# WIFI_module.net
KiCad netlist of a schematic drawn in Altium Designer
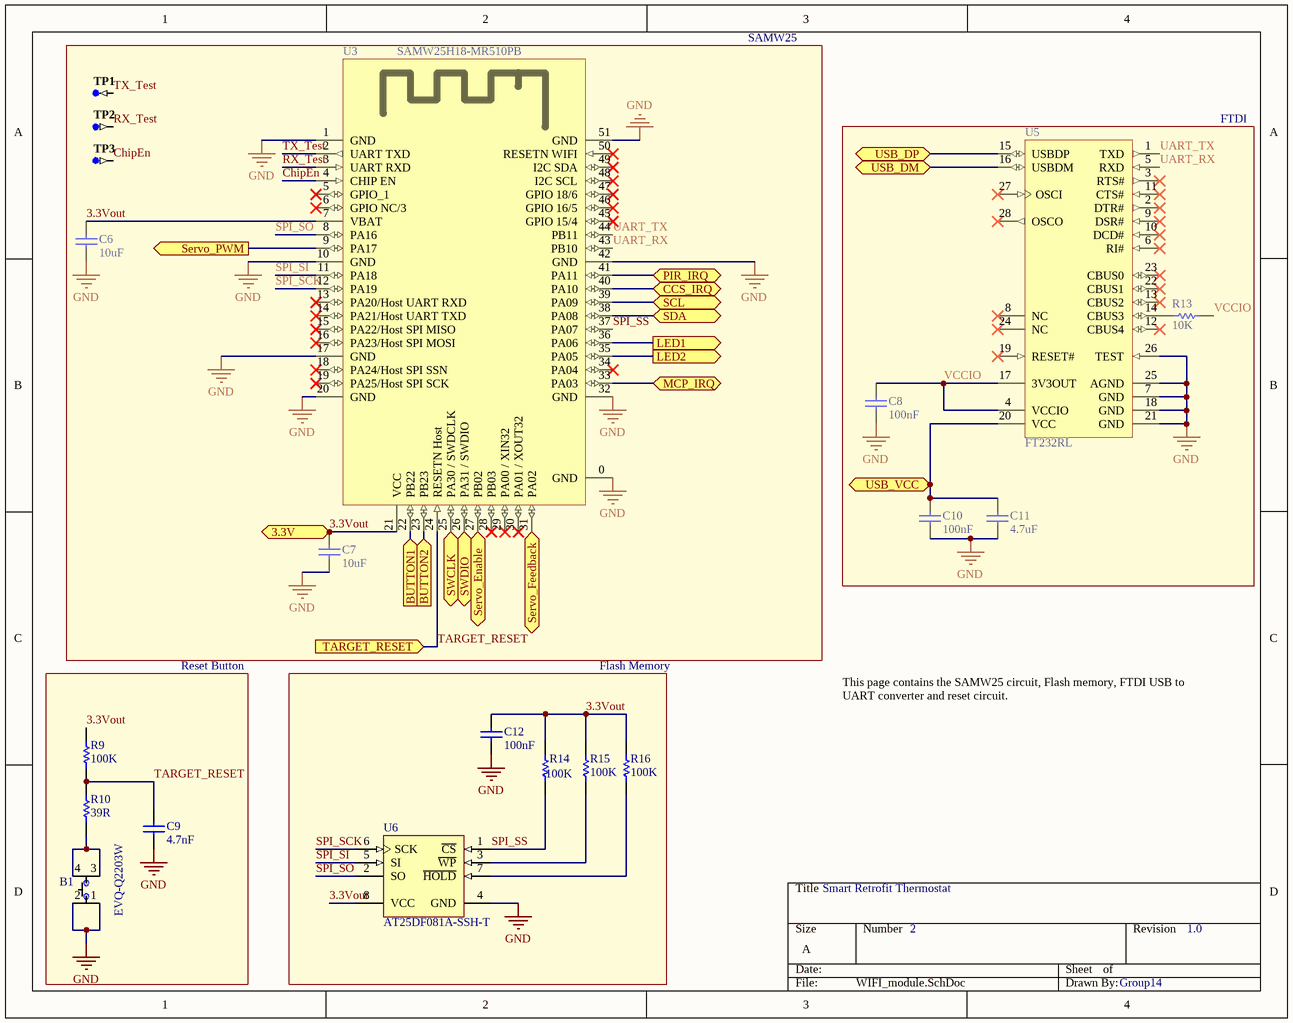
[diagram p0: WIFI_module.SchDoc]

(export (version "E")
  (design (tool "Eeschema 10.0.6"))
  (components
    (comp (ref "B1")
      (value "EVQ-Q2203W")
      (footprint "EVQ-Q2203W")
      (description "SWITCH TACTILE SPST-NO 0.02A 15V")
      (fields (field (name "MANUFACTURER") "Panasonic Electronic Components"))
      (libsource (lib "ese516_baseComponents") (part "EVQ-Q2203W"))
    )
    (comp (ref "C6")
      (value "10uF")
      (footprint "CAPC0805(2012)100_L")
      (description "CAP 10uF 16V ±20% 0805 (2012 Metric) Thickness 1mm SMD")
      (fields (field (name "TOLERANCE") "Â±20%"))
      (libsource (lib "Altium Content Vault") (part "CMP-1036-04930-1"))
    )
    (comp (ref "C7")
      (value "10uF")
      (footprint "CAPC0805(2012)100_L")
      (description "CAP 10uF 16V ±20% 0805 (2012 Metric) Thickness 1mm SMD")
      (fields (field (name "TOLERANCE") "Â±20%"))
      (libsource (lib "Altium Content Vault") (part "CMP-1036-04930-1"))
    )
    (comp (ref "C8")
      (value "100nF")
      (footprint "CAPC0805(2012)145_M")
      (description "CAP 100nF 16V ±20% 0805 (2012 Metric) Thickness 1.45mm SMD")
      (fields (field (name "TOLERANCE") "Â±20%"))
      (libsource (lib "Altium Content Vault") (part "CAP"))
    )
    (comp (ref "C9")
      (value "4.7nF")
      (footprint "CAPC0805(2012)100_L")
      (description "CAP 4.7nF 16V ±20% 0805 (2012 Metric) Thickness 1mm SMD")
      (fields (field (name "TOLERANCE") "Â±20%"))
      (libsource (lib "Altium Content Vault") (part "CAP"))
    )
    (comp (ref "C10")
      (value "100nF")
      (footprint "CAPC0805(2012)145_M")
      (description "CAP 100nF 16V ±20% 0805 (2012 Metric) Thickness 1.45mm SMD")
      (fields (field (name "TOLERANCE") "Â±20%"))
      (libsource (lib "Altium Content Vault") (part "CAP"))
    )
    (comp (ref "C11")
      (value "4.7uF")
      (footprint "CAPC0805(2012)155_L")
      (description "CAP 4.7uF 10V ±10% 0805 (2012 Metric) Thickness 1.55mm SMD")
      (fields (field (name "TOLERANCE") "Â±10%"))
      (libsource (lib "Altium Content Vault") (part "CAP"))
    )
    (comp (ref "C12")
      (value "100nF")
      (footprint "CAPC0805(2012)145_M")
      (description "CAP 100nF 16V ±20% 0805 (2012 Metric) Thickness 1.45mm SMD")
      (fields (field (name "TOLERANCE") "Â±20%"))
      (libsource (lib "Altium Content Vault") (part "CAP"))
    )
    (comp (ref "R9")
      (value "100K")
      (footprint "RESC0805(2012)_L")
      (description "100K 0.125W 1% 0805 (2012 Metric)  SMD")
      (fields (field (name "POWER") "0.125 W") (field (name "TOLERANCE") "1 %"))
      (libsource (lib "Altium Content Vault") (part "RES"))
    )
    (comp (ref "R10")
      (value "39R")
      (footprint "RESC0805(2012)_N")
      (description "39R 0.125W 1% 0805 (2012 Metric)  SMD")
      (fields (field (name "POWER") "0.125 W") (field (name "TOLERANCE") "1 %"))
      (libsource (lib "Altium Content Vault") (part "RES"))
    )
    (comp (ref "R13")
      (value "10K")
      (footprint "RESC0805(2012)_M")
      (description "10K 0.125W 1% 0805 (2012 Metric)  SMD")
      (fields (field (name "POWER") "0.125 W") (field (name "TOLERANCE") "1 %"))
      (libsource (lib "Altium Content Vault") (part "RES"))
    )
    (comp (ref "R14")
      (value "100K")
      (footprint "RESC0805(2012)_L")
      (description "100K 0.125W 1% 0805 (2012 Metric)  SMD")
      (fields (field (name "POWER") "0.125 W") (field (name "TOLERANCE") "1 %"))
      (libsource (lib "Altium Content Vault") (part "RES"))
    )
    (comp (ref "R15")
      (value "100K")
      (footprint "RESC0805(2012)_L")
      (description "100K 0.125W 1% 0805 (2012 Metric)  SMD")
      (fields (field (name "POWER") "0.125 W") (field (name "TOLERANCE") "1 %"))
      (libsource (lib "Altium Content Vault") (part "RES"))
    )
    (comp (ref "R16")
      (value "100K")
      (footprint "RESC0805(2012)_L")
      (description "100K 0.125W 1% 0805 (2012 Metric)  SMD")
      (fields (field (name "POWER") "0.125 W") (field (name "TOLERANCE") "1 %"))
      (libsource (lib "Altium Content Vault") (part "RES"))
    )
    (comp (ref "TP1")
      (value "~")
      (footprint "TP-SM-C-100")
      (description "Test Point, Surface Mount, Circular, Pad Diameter 1 mm")
      (fields (field (name "PARTNUMBER") "TP-SM-C-100") (field (name "MANUFACTURER") "No Vendor"))
      (libsource (lib "Altium Content Vault") (part "CMP-0484-00002-2"))
    )
    (comp (ref "TP2")
      (value "~")
      (footprint "TP-SM-C-100")
      (description "Test Point, Surface Mount, Circular, Pad Diameter 1 mm")
      (fields (field (name "PARTNUMBER") "TP-SM-C-100") (field (name "MANUFACTURER") "No Vendor"))
      (libsource (lib "Altium Content Vault") (part "CMP-0484-00002-2"))
    )
    (comp (ref "TP3")
      (value "~")
      (footprint "TP-SM-C-100")
      (description "Test Point, Surface Mount, Circular, Pad Diameter 1 mm")
      (fields (field (name "PARTNUMBER") "TP-SM-C-100") (field (name "MANUFACTURER") "No Vendor"))
      (libsource (lib "Altium Content Vault") (part "CMP-0484-00002-2"))
    )
    (comp (ref "U3")
      (value "SAMW25H18-MR510PB")
      (footprint "SAMW25H18-MR510PB")
      (description "RF TXRX MODULE WIFI TRACE ANT")
      (fields
        (field (name "MANUFACTURER") "Atmel")
        (field (name "MANUFACTURER PART NUMBER") "ATSAMW25H18-MR510PB")
      )
      (libsource (lib "ese516_baseComponents") (part "SAMW25H18-MR510PB"))
    )
    (comp (ref "U5")
      (value "FT232RL")
      (footprint "FTDI-SSOP-28_M")
      (description "IC USB FS SERIAL UART 28-SSOP")
      (fields (field (name "MANUFACTURER") "FTDI"))
      (libsource (lib "Altium Content Vault") (part "FTDI-FT232-SSOP-28"))
    )
    (comp (ref "U6")
      (value "AT25DF081A-SSH-T")
      (footprint "AT25DF081A-SSH-T")
      (description "IC FLASH 8MBIT 100MHZ 8SOIC")
      (fields (field (name "MANUFACTURER") "Adesto Technologies"))
      (libsource (lib "ese516_baseComponents") (part "AT25DF081A-SSH-T"))
    )
  )
  (nets
    (net (code "1") (name "/3.3Vout") (class "Default")
      (node (ref "C12") (pin "2") (pinfunction "2_2") (pintype "passive"))
      (node (ref "C6") (pin "2") (pinfunction "2_2") (pintype "passive"))
      (node (ref "C7") (pin "2") (pinfunction "2_2") (pintype "passive"))
      (node (ref "R14") (pin "1") (pinfunction "1_1") (pintype "passive"))
      (node (ref "R15") (pin "1") (pinfunction "1_1") (pintype "passive"))
      (node (ref "R16") (pin "1") (pinfunction "1_1") (pintype "passive"))
      (node (ref "R9") (pin "1") (pinfunction "1_1") (pintype "passive"))
      (node (ref "U3") (pin "21") (pinfunction "VCC_21") (pintype "power_in"))
      (node (ref "U3") (pin "7") (pinfunction "VBAT_7") (pintype "power_in"))
      (node (ref "U6") (pin "8") (pinfunction "VCC_8") (pintype "power_in"))
    )
    (net (code "2") (name "/BUTTON1") (class "Default")
      (node (ref "U3") (pin "22") (pinfunction "PB22_22") (pintype "bidirectional"))
    )
    (net (code "3") (name "/BUTTON2") (class "Default")
      (node (ref "U3") (pin "23") (pinfunction "PB23_23") (pintype "bidirectional"))
    )
    (net (code "4") (name "/CCS_IRQ") (class "Default")
      (node (ref "U3") (pin "40") (pinfunction "PA10_40") (pintype "bidirectional"))
    )
    (net (code "5") (name "/ChipEn") (class "Default")
      (node (ref "TP3") (pin "1") (pinfunction "1_1") (pintype "output"))
      (node (ref "U3") (pin "4") (pinfunction "CHIP_EN_4") (pintype "input"))
    )
    (net (code "6") (name "/LED1") (class "Default")
      (node (ref "U3") (pin "36") (pinfunction "PA06_36") (pintype "bidirectional"))
    )
    (net (code "7") (name "/LED2") (class "Default")
      (node (ref "U3") (pin "35") (pinfunction "PA05_35") (pintype "bidirectional"))
    )
    (net (code "8") (name "/MCP_IRQ") (class "Default")
      (node (ref "U3") (pin "33") (pinfunction "PA03_33") (pintype "bidirectional"))
    )
    (net (code "9") (name "/PIR_IRQ") (class "Default")
      (node (ref "U3") (pin "41") (pinfunction "PA11_41") (pintype "bidirectional"))
    )
    (net (code "10") (name "/RX_Test") (class "Default")
      (node (ref "TP2") (pin "1") (pinfunction "1_1") (pintype "output"))
      (node (ref "U3") (pin "3") (pinfunction "UART_RXD_3") (pintype "input"))
    )
    (net (code "11") (name "/SCL") (class "Default")
      (node (ref "U3") (pin "39") (pinfunction "PA09_39") (pintype "bidirectional"))
    )
    (net (code "12") (name "/SDA") (class "Default")
      (node (ref "U3") (pin "38") (pinfunction "PA08_38") (pintype "bidirectional"))
    )
    (net (code "13") (name "/SPI_SCK") (class "Default")
      (node (ref "U3") (pin "12") (pinfunction "PA19_12") (pintype "bidirectional"))
      (node (ref "U6") (pin "6") (pinfunction "SCK_6") (pintype "input"))
    )
    (net (code "14") (name "/SPI_SI") (class "Default")
      (node (ref "U3") (pin "11") (pinfunction "PA18_11") (pintype "bidirectional"))
      (node (ref "U6") (pin "5") (pinfunction "SI_5") (pintype "input"))
    )
    (net (code "15") (name "/SPI_SO") (class "Default")
      (node (ref "U3") (pin "8") (pinfunction "PA16_8") (pintype "bidirectional"))
      (node (ref "U6") (pin "2") (pinfunction "SO_2") (pintype "tri_state"))
    )
    (net (code "16") (name "/SPI_SS") (class "Default")
      (node (ref "R14") (pin "2") (pinfunction "2_2") (pintype "passive"))
      (node (ref "U3") (pin "37") (pinfunction "PA07_37") (pintype "bidirectional"))
      (node (ref "U6") (pin "1") (pinfunction "~{CS}_1") (pintype "input"))
    )
    (net (code "17") (name "/SWCLK") (class "Default")
      (node (ref "U3") (pin "25") (pinfunction "PA30_/_SWDCLK_25") (pintype "bidirectional"))
    )
    (net (code "18") (name "/SWDIO") (class "Default")
      (node (ref "U3") (pin "26") (pinfunction "PA31_/_SWDIO_26") (pintype "bidirectional"))
    )
    (net (code "19") (name "/Servo_Enable") (class "Default")
      (node (ref "U3") (pin "27") (pinfunction "PB02_27") (pintype "bidirectional"))
    )
    (net (code "20") (name "/Servo_Feedback") (class "Default")
      (node (ref "U3") (pin "31") (pinfunction "PA02_31") (pintype "bidirectional"))
    )
    (net (code "21") (name "/Servo_PWM") (class "Default")
      (node (ref "U3") (pin "9") (pinfunction "PA17_9") (pintype "bidirectional"))
    )
    (net (code "22") (name "/TARGET_RESET") (class "Default")
      (node (ref "C9") (pin "2") (pinfunction "2_2") (pintype "passive"))
      (node (ref "R10") (pin "1") (pinfunction "1_1") (pintype "passive"))
      (node (ref "R9") (pin "2") (pinfunction "2_2") (pintype "passive"))
      (node (ref "U3") (pin "24") (pinfunction "RESETN_Host_24") (pintype "input"))
    )
    (net (code "23") (name "/TX_Test") (class "Default")
      (node (ref "TP1") (pin "1") (pinfunction "1_1") (pintype "output"))
      (node (ref "U3") (pin "2") (pinfunction "UART_TXD_2") (pintype "output"))
    )
    (net (code "24") (name "/UART_RX") (class "Default")
      (node (ref "U3") (pin "43") (pinfunction "PB10_43") (pintype "bidirectional"))
      (node (ref "U5") (pin "5") (pinfunction "RXD_5") (pintype "input"))
    )
    (net (code "25") (name "/UART_TX") (class "Default")
      (node (ref "U3") (pin "44") (pinfunction "PB11_44") (pintype "bidirectional"))
      (node (ref "U5") (pin "1") (pinfunction "TXD_1") (pintype "output"))
    )
    (net (code "26") (name "/USB_DM") (class "Default")
      (node (ref "U5") (pin "16") (pinfunction "USBDM_16") (pintype "bidirectional"))
    )
    (net (code "27") (name "/USB_DP") (class "Default")
      (node (ref "U5") (pin "15") (pinfunction "USBDP_15") (pintype "bidirectional"))
    )
    (net (code "28") (name "/USB_VCC") (class "Default")
      (node (ref "C10") (pin "2") (pinfunction "2_2") (pintype "passive"))
      (node (ref "C11") (pin "2") (pinfunction "2_2") (pintype "passive"))
      (node (ref "U5") (pin "20") (pinfunction "VCC_20") (pintype "power_in"))
    )
    (net (code "29") (name "/VCCIO") (class "Default")
      (node (ref "C8") (pin "2") (pinfunction "2_2") (pintype "passive"))
      (node (ref "R13") (pin "2") (pinfunction "2_2") (pintype "passive"))
      (node (ref "U5") (pin "17") (pinfunction "3V3OUT_17") (pintype "power_in"))
      (node (ref "U5") (pin "4") (pinfunction "VCCIO_4") (pintype "power_in"))
    )
    (net (code "30") (name "GND") (class "Default")
      (node (ref "B1") (pin "1") (pinfunction "1_1") (pintype "power_in"))
      (node (ref "B1") (pin "2") (pinfunction "2_2") (pintype "power_in"))
      (node (ref "C10") (pin "1") (pinfunction "1_1") (pintype "passive"))
      (node (ref "C11") (pin "1") (pinfunction "1_1") (pintype "passive"))
      (node (ref "C12") (pin "1") (pinfunction "1_1") (pintype "passive"))
      (node (ref "C6") (pin "1") (pinfunction "1_1") (pintype "passive"))
      (node (ref "C7") (pin "1") (pinfunction "1_1") (pintype "passive"))
      (node (ref "C8") (pin "1") (pinfunction "1_1") (pintype "passive"))
      (node (ref "C9") (pin "1") (pinfunction "1_1") (pintype "passive"))
      (node (ref "U3") (pin "0") (pinfunction "GND_0") (pintype "power_in"))
      (node (ref "U3") (pin "1") (pinfunction "GND_1") (pintype "power_in"))
      (node (ref "U3") (pin "10") (pinfunction "GND_10") (pintype "power_in"))
      (node (ref "U3") (pin "17") (pinfunction "GND_17") (pintype "power_in"))
      (node (ref "U3") (pin "20") (pinfunction "GND_20") (pintype "power_in"))
      (node (ref "U3") (pin "32") (pinfunction "GND_32") (pintype "power_in"))
      (node (ref "U3") (pin "42") (pinfunction "GND_42") (pintype "power_in"))
      (node (ref "U3") (pin "51") (pinfunction "GND_51") (pintype "power_in"))
      (node (ref "U5") (pin "18") (pinfunction "GND_18") (pintype "power_in"))
      (node (ref "U5") (pin "21") (pinfunction "GND_21") (pintype "power_in"))
      (node (ref "U5") (pin "25") (pinfunction "AGND_25") (pintype "power_in"))
      (node (ref "U5") (pin "26") (pinfunction "TEST_26") (pintype "input"))
      (node (ref "U5") (pin "7") (pinfunction "GND_7") (pintype "power_in"))
      (node (ref "U6") (pin "4") (pinfunction "GND_4") (pintype "power_in"))
    )
    (net (code "31") (name "Net-(B1-Pad3)") (class "Default")
      (node (ref "B1") (pin "3") (pinfunction "3_3") (pintype "power_in"))
      (node (ref "B1") (pin "4") (pinfunction "4_4") (pintype "power_in"))
      (node (ref "R10") (pin "2") (pinfunction "2_2") (pintype "passive"))
    )
    (net (code "32") (name "Net-(U5-CBUS3)") (class "Default")
      (node (ref "R13") (pin "1") (pinfunction "1_1") (pintype "passive"))
      (node (ref "U5") (pin "14") (pinfunction "CBUS3_14") (pintype "bidirectional"))
    )
    (net (code "33") (name "Net-(U6-~{HOLD})") (class "Default")
      (node (ref "R16") (pin "2") (pinfunction "2_2") (pintype "passive"))
      (node (ref "U6") (pin "7") (pinfunction "~{HOLD}_7") (pintype "input"))
    )
    (net (code "34") (name "Net-(U6-~{WP})") (class "Default")
      (node (ref "R15") (pin "2") (pinfunction "2_2") (pintype "passive"))
      (node (ref "U6") (pin "3") (pinfunction "~{WP}_3") (pintype "input"))
    )
    (net (code "35") (name "unconnected-(U3-GPIO_1-Pad5)") (class "Default")
      (node (ref "U3") (pin "5") (pinfunction "GPIO_1_5") (pintype "bidirectional+no_connect"))
    )
    (net (code "36") (name "unconnected-(U3-GPIO_15{slash}4-Pad45)") (class "Default")
      (node (ref "U3") (pin "45") (pinfunction "GPIO_15/4_45") (pintype "bidirectional+no_connect"))
    )
    (net (code "37") (name "unconnected-(U3-GPIO_16{slash}5-Pad46)") (class "Default")
      (node (ref "U3") (pin "46") (pinfunction "GPIO_16/5_46") (pintype "bidirectional+no_connect"))
    )
    (net (code "38") (name "unconnected-(U3-GPIO_18{slash}6-Pad47)") (class "Default")
      (node (ref "U3") (pin "47") (pinfunction "GPIO_18/6_47") (pintype "bidirectional+no_connect"))
    )
    (net (code "39") (name "unconnected-(U3-GPIO_NC{slash}3-Pad6)") (class "Default")
      (node (ref "U3") (pin "6") (pinfunction "GPIO_NC/3_6") (pintype "bidirectional+no_connect"))
    )
    (net (code "40") (name "unconnected-(U3-I2C_SCL-Pad48)") (class "Default")
      (node (ref "U3") (pin "48") (pinfunction "I2C_SCL_48") (pintype "bidirectional+no_connect"))
    )
    (net (code "41") (name "unconnected-(U3-I2C_SDA-Pad49)") (class "Default")
      (node (ref "U3") (pin "49") (pinfunction "I2C_SDA_49") (pintype "bidirectional+no_connect"))
    )
    (net (code "42") (name "unconnected-(U3-PA00_{slash}_XIN32-Pad29)") (class "Default")
      (node (ref "U3") (pin "29") (pinfunction "PA00_/_XIN32_29") (pintype "bidirectional+no_connect"))
    )
    (net (code "43") (name "unconnected-(U3-PA01_{slash}_XOUT32-Pad30)") (class "Default")
      (node (ref "U3") (pin "30") (pinfunction "PA01_/_XOUT32_30") (pintype "bidirectional+no_connect"))
    )
    (net (code "44") (name "unconnected-(U3-PA04-Pad34)") (class "Default")
      (node (ref "U3") (pin "34") (pinfunction "PA04_34") (pintype "bidirectional+no_connect"))
    )
    (net (code "45") (name "unconnected-(U3-PA20{slash}Host_UART_RXD-Pad13)") (class "Default")
      (node (ref "U3") (pin "13") (pinfunction "PA20/Host_UART_RXD_13") (pintype "bidirectional+no_connect"))
    )
    (net (code "46") (name "unconnected-(U3-PA21{slash}Host_UART_TXD-Pad14)") (class "Default")
      (node (ref "U3") (pin "14") (pinfunction "PA21/Host_UART_TXD_14") (pintype "bidirectional+no_connect"))
    )
    (net (code "47") (name "unconnected-(U3-PA22{slash}Host_SPI_MISO-Pad15)") (class "Default")
      (node (ref "U3") (pin "15") (pinfunction "PA22/Host_SPI_MISO_15") (pintype "bidirectional+no_connect"))
    )
    (net (code "48") (name "unconnected-(U3-PA23{slash}Host_SPI_MOSI-Pad16)") (class "Default")
      (node (ref "U3") (pin "16") (pinfunction "PA23/Host_SPI_MOSI_16") (pintype "bidirectional+no_connect"))
    )
    (net (code "49") (name "unconnected-(U3-PA24{slash}Host_SPI_SSN-Pad18)") (class "Default")
      (node (ref "U3") (pin "18") (pinfunction "PA24/Host_SPI_SSN_18") (pintype "bidirectional+no_connect"))
    )
    (net (code "50") (name "unconnected-(U3-PA25{slash}Host_SPI_SCK-Pad19)") (class "Default")
      (node (ref "U3") (pin "19") (pinfunction "PA25/Host_SPI_SCK_19") (pintype "bidirectional+no_connect"))
    )
    (net (code "51") (name "unconnected-(U3-PB03-Pad28)") (class "Default")
      (node (ref "U3") (pin "28") (pinfunction "PB03_28") (pintype "bidirectional+no_connect"))
    )
    (net (code "52") (name "unconnected-(U3-RESETN_WIFI-Pad50)") (class "Default")
      (node (ref "U3") (pin "50") (pinfunction "RESETN_WIFI_50") (pintype "input+no_connect"))
    )
    (net (code "53") (name "unconnected-(U5-CBUS0-Pad23)") (class "Default")
      (node (ref "U5") (pin "23") (pinfunction "CBUS0_23") (pintype "bidirectional+no_connect"))
    )
    (net (code "54") (name "unconnected-(U5-CBUS1-Pad22)") (class "Default")
      (node (ref "U5") (pin "22") (pinfunction "CBUS1_22") (pintype "bidirectional+no_connect"))
    )
    (net (code "55") (name "unconnected-(U5-CBUS2-Pad13)") (class "Default")
      (node (ref "U5") (pin "13") (pinfunction "CBUS2_13") (pintype "bidirectional+no_connect"))
    )
    (net (code "56") (name "unconnected-(U5-CBUS4-Pad12)") (class "Default")
      (node (ref "U5") (pin "12") (pinfunction "CBUS4_12") (pintype "bidirectional+no_connect"))
    )
    (net (code "57") (name "unconnected-(U5-CTS#-Pad11)") (class "Default")
      (node (ref "U5") (pin "11") (pinfunction "CTS#_11") (pintype "input+no_connect"))
    )
    (net (code "58") (name "unconnected-(U5-DCD#-Pad10)") (class "Default")
      (node (ref "U5") (pin "10") (pinfunction "DCD#_10") (pintype "input+no_connect"))
    )
    (net (code "59") (name "unconnected-(U5-DSR#-Pad9)") (class "Default")
      (node (ref "U5") (pin "9") (pinfunction "DSR#_9") (pintype "input+no_connect"))
    )
    (net (code "60") (name "unconnected-(U5-DTR#-Pad2)") (class "Default")
      (node (ref "U5") (pin "2") (pinfunction "DTR#_2") (pintype "output+no_connect"))
    )
    (net (code "61") (name "unconnected-(U5-NC-Pad8)") (class "Default")
      (node (ref "U5") (pin "8") (pinfunction "NC_8") (pintype "passive+no_connect"))
    )
    (net (code "62") (name "unconnected-(U5-NC-Pad24)") (class "Default")
      (node (ref "U5") (pin "24") (pinfunction "NC_24") (pintype "passive+no_connect"))
    )
    (net (code "63") (name "unconnected-(U5-OSCI-Pad27)") (class "Default")
      (node (ref "U5") (pin "27") (pinfunction "OSCI_27") (pintype "input+no_connect"))
    )
    (net (code "64") (name "unconnected-(U5-OSCO-Pad28)") (class "Default")
      (node (ref "U5") (pin "28") (pinfunction "OSCO_28") (pintype "output+no_connect"))
    )
    (net (code "65") (name "unconnected-(U5-RESET#-Pad19)") (class "Default")
      (node (ref "U5") (pin "19") (pinfunction "RESET#_19") (pintype "input+no_connect"))
    )
    (net (code "66") (name "unconnected-(U5-RI#-Pad6)") (class "Default")
      (node (ref "U5") (pin "6") (pinfunction "RI#_6") (pintype "input+no_connect"))
    )
    (net (code "67") (name "unconnected-(U5-RTS#-Pad3)") (class "Default")
      (node (ref "U5") (pin "3") (pinfunction "RTS#_3") (pintype "output+no_connect"))
    )
  )
)
